# I2C_Real_Time_Clock.net
KiCad netlist of a schematic drawn in Altium Designer
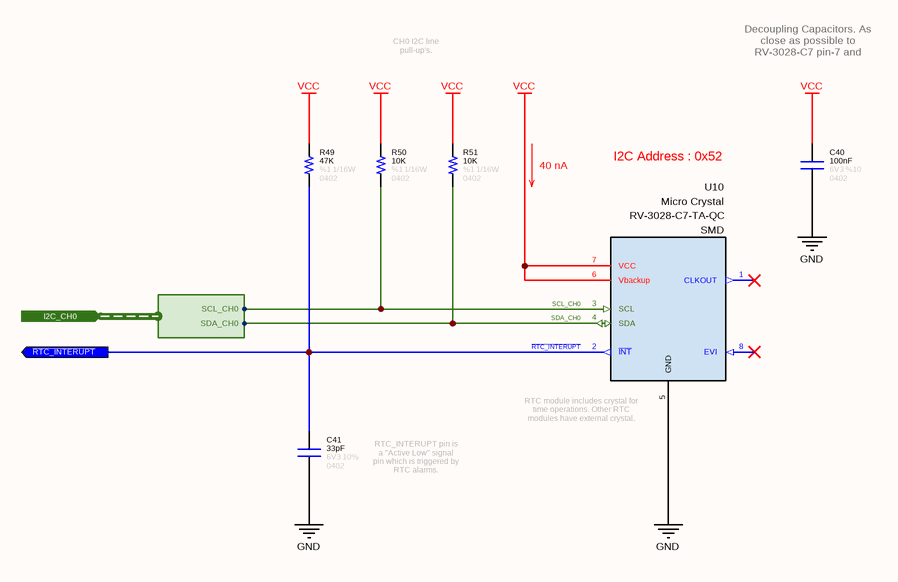
[diagram p0: I2C Real Time Clock.SchDoc]

(export (version "E")
  (design (tool "Eeschema 10.0.6"))
  (components
    (comp (ref "C40")
      (value "100nF")
      (footprint "CAPACITOR_0402")
      (description "Capacitor - 100nF [0402-6V3] (Ceramic)")
      (fields
        (field (name "MANUFACTURER PART NUMBER") "04026D104KAT4A")
        (field (name "TOLERANCE") "%10")
        (field (name "VOLTAGE") "6V3")
        (field (name "CASE") "0402")
        (field (name "Comment") "Capacitor - 100nF [0402] (Ceramic)")
      )
      (libsource (lib "P101DA_Library") (part "Capacitor - 100nF [0402-6V3]"))
    )
    (comp (ref "C41")
      (value "33pF")
      (footprint "CAPACITOR_0402")
      (description "Capacitor - 33pF [0402] (Ceramic)")
      (fields
        (field (name "MANUFACTURER PART NUMBER") "C0402C330J9RACAUTO")
        (field (name "TOLERANCE") "10%")
        (field (name "CASE") "0402")
        (field (name "VOLTAGE") "6V3")
      )
      (libsource (lib "P101DA_Library") (part "Capacitor - 33pF [0402-6V3]"))
    )
    (comp (ref "R49")
      (value "47K")
      (footprint "RESISTOR_0402")
      (description "Thick Film Resistors - SMD 1/16 W 47 KOhm 1%")
      (fields
        (field (name "MANUFACTURER PART NUMBER") "CRCW040247K0FKED")
        (field (name "TOLERANCE") "%1")
        (field (name "CASE") "0402")
        (field (name "POWER") "1/16W")
        (field (name "Comment") "47K - 0402 - %1 - 1/16W")
      )
      (libsource (lib "P101DA_Library") (part "Resistor - 47K [0402]"))
    )
    (comp (ref "R50")
      (value "10K")
      (footprint "RESISTOR_0402")
      (description "Thick Film Resistors - SMD 1/16 W 10 KOhm 1%")
      (fields
        (field (name "MANUFACTURER PART NUMBER") "CRCW040210K0FKED")
        (field (name "TOLERANCE") "%1")
        (field (name "CASE") "0402")
        (field (name "POWER") "1/16W")
        (field (name "Comment") "10K - 0402 - %1 - 1/16W")
      )
      (libsource (lib "P101DA_Library") (part "Resistor - 10K [0402]"))
    )
    (comp (ref "R51")
      (value "10K")
      (footprint "RESISTOR_0402")
      (description "Thick Film Resistors - SMD 1/16 W 10 KOhm 1%")
      (fields
        (field (name "MANUFACTURER PART NUMBER") "CRCW040210K0FKED")
        (field (name "TOLERANCE") "%1")
        (field (name "CASE") "0402")
        (field (name "POWER") "1/16W")
        (field (name "Comment") "10K - 0402 - %1 - 1/16W")
      )
      (libsource (lib "P101DA_Library") (part "Resistor - 10K [0402]"))
    )
    (comp (ref "U10")
      (value "RV-3028-C7 32.768KHZ 1PPM TA QC")
      (footprint "RV-3028-C7")
      (description "IC Rtc Clk/calendar I2C 8-SMT")
      (fields
        (field (name "MANUFACTURER NAME") "Micro Crystal")
        (field (name "MANUFACTURER PART NUMBER") "RV-3028-C7-TA-QC")
        (field (name "CASE") "SMD")
      )
      (libsource (lib "P101DA_Library") (part "IC - RV-3028-C7"))
    )
  )
  (nets
    (net (code "2") (name "/SCL_CH0") (class "Default")
      (node (ref "R50") (pin "1") (pinfunction "1_1") (pintype "passive"))
      (node (ref "U10") (pin "3") (pinfunction "SCL_3") (pintype "input"))
    )
    (net (code "3") (name "/SDA_CH0") (class "Default")
      (node (ref "R51") (pin "1") (pinfunction "1_1") (pintype "passive"))
      (node (ref "U10") (pin "4") (pinfunction "SDA_4") (pintype "bidirectional"))
    )
    (net (code "5") (name "/~{RTC_INTERUPT}") (class "Default")
      (node (ref "C41") (pin "2") (pinfunction "2_2") (pintype "passive"))
      (node (ref "R49") (pin "1") (pinfunction "1_1") (pintype "passive"))
      (node (ref "U10") (pin "2") (pinfunction "~{INT}_2") (pintype "output"))
    )
    (net (code "6") (name "GND") (class "Default")
      (node (ref "C40") (pin "1") (pinfunction "1_1") (pintype "passive"))
      (node (ref "C41") (pin "1") (pinfunction "1_1") (pintype "passive"))
      (node (ref "U10") (pin "5") (pinfunction "GND_5") (pintype "power_in"))
    )
    (net (code "7") (name "VCC") (class "Default")
      (node (ref "C40") (pin "2") (pinfunction "2_2") (pintype "passive"))
      (node (ref "R49") (pin "2") (pinfunction "2_2") (pintype "passive"))
      (node (ref "R50") (pin "2") (pinfunction "2_2") (pintype "passive"))
      (node (ref "R51") (pin "2") (pinfunction "2_2") (pintype "passive"))
      (node (ref "U10") (pin "6") (pinfunction "Vbackup_6") (pintype "power_in"))
      (node (ref "U10") (pin "7") (pinfunction "VCC_7") (pintype "power_in"))
    )
    (net (code "8") (name "unconnected-(U10-CLKOUT-Pad1)") (class "Default")
      (node (ref "U10") (pin "1") (pinfunction "CLKOUT_1") (pintype "output+no_connect"))
    )
    (net (code "9") (name "unconnected-(U10-EVI-Pad8)") (class "Default")
      (node (ref "U10") (pin "8") (pinfunction "EVI_8") (pintype "input+no_connect"))
    )
  )
)
